# Wireless_Motor_Driver_Shield.net
KiCad netlist of a schematic drawn in EAGLE
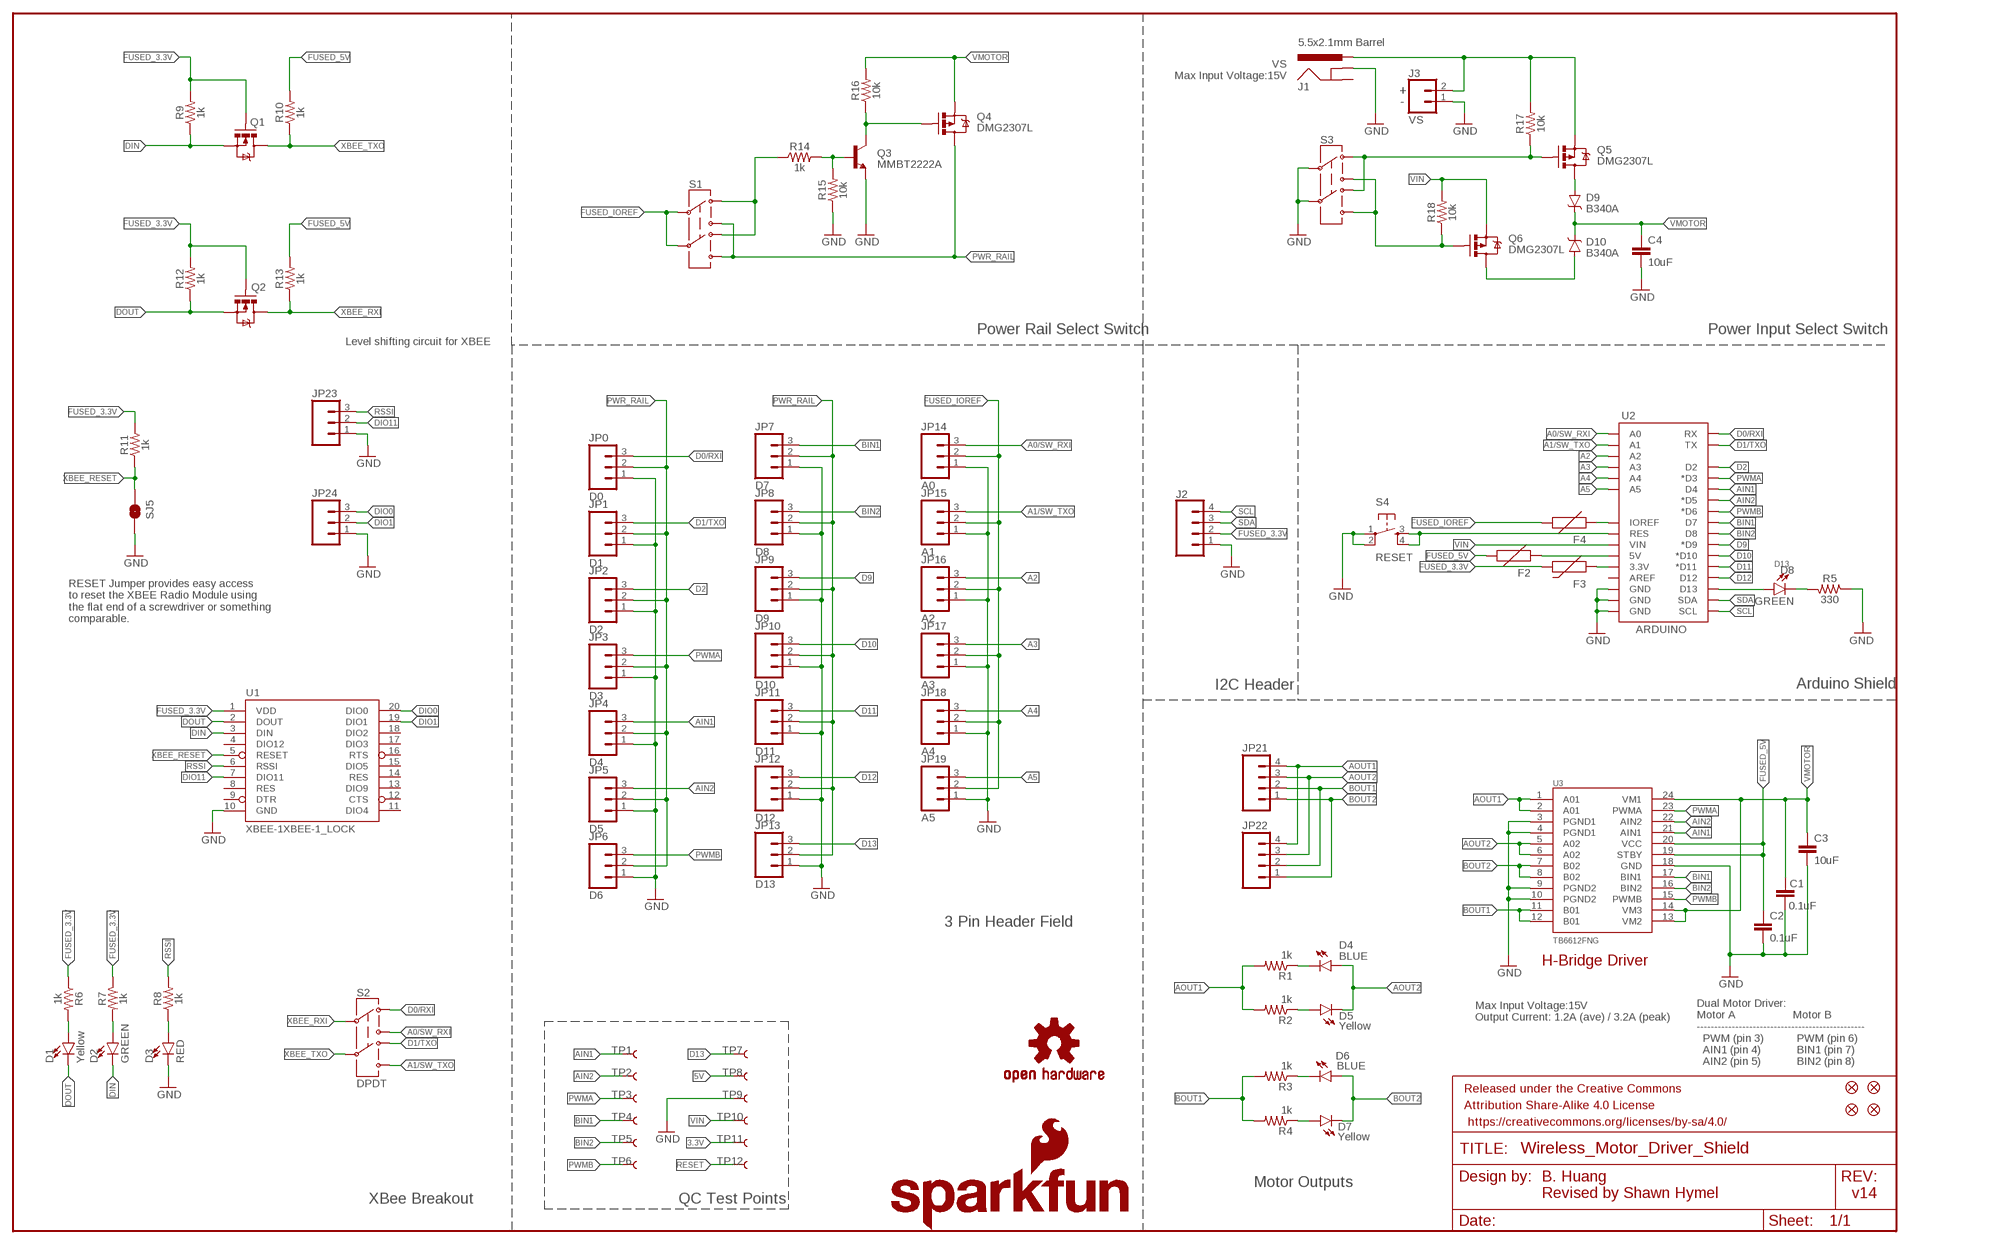
[diagram p0: schematic, sheet 1]

(export (version "E")
  (design (tool "Eeschema 10.0.6"))
  (components
    (comp (ref "C1")
      (value "0.1uF")
      (footprint "eagle-import:0603")
      (libsource (lib "eagle-import") (part "0.1UF-0603-25V-5%"))
    )
    (comp (ref "C2")
      (value "0.1uF")
      (footprint "eagle-import:0603")
      (libsource (lib "eagle-import") (part "0.1UF-0603-25V-5%"))
    )
    (comp (ref "C3")
      (value "10uF")
      (footprint "eagle-import:1210")
      (libsource (lib "eagle-import") (part "10UF-1210-50V-20%"))
    )
    (comp (ref "C4")
      (value "10uF")
      (footprint "eagle-import:1210")
      (libsource (lib "eagle-import") (part "10UF-1210-50V-20%"))
    )
    (comp (ref "D1")
      (value "Yellow")
      (footprint "eagle-import:LED-0603")
      (libsource (lib "eagle-import") (part "LED-YELLOW0603"))
    )
    (comp (ref "D2")
      (value "GREEN")
      (footprint "eagle-import:LED-0603")
      (libsource (lib "eagle-import") (part "LED-GREEN0603"))
    )
    (comp (ref "D3")
      (value "RED")
      (footprint "eagle-import:LED-0603")
      (libsource (lib "eagle-import") (part "LED-RED0603"))
    )
    (comp (ref "D4")
      (value "BLUE")
      (footprint "eagle-import:LED-0603")
      (libsource (lib "eagle-import") (part "LED-BLUE0603"))
    )
    (comp (ref "D5")
      (value "Yellow")
      (footprint "eagle-import:LED-0603")
      (libsource (lib "eagle-import") (part "LED-YELLOW0603"))
    )
    (comp (ref "D6")
      (value "BLUE")
      (footprint "eagle-import:LED-0603")
      (libsource (lib "eagle-import") (part "LED-BLUE0603"))
    )
    (comp (ref "D7")
      (value "Yellow")
      (footprint "eagle-import:LED-0603")
      (libsource (lib "eagle-import") (part "LED-YELLOW0603"))
    )
    (comp (ref "D8")
      (value "GREEN")
      (footprint "eagle-import:LED-0603")
      (libsource (lib "eagle-import") (part "LED-GREEN0603"))
    )
    (comp (ref "D9")
      (value "B340A")
      (footprint "eagle-import:SMA-DIODE")
      (libsource (lib "eagle-import") (part "DIODE-SCHOTTKY-B340A"))
    )
    (comp (ref "D10")
      (value "B340A")
      (footprint "eagle-import:SMA-DIODE")
      (libsource (lib "eagle-import") (part "DIODE-SCHOTTKY-B340A"))
    )
    (comp (ref "F2")
      (value "PTCSMD")
      (footprint "eagle-import:PTC-1206")
      (libsource (lib "eagle-import") (part "PTCSMD"))
    )
    (comp (ref "F3")
      (value "PTCSMD")
      (footprint "eagle-import:PTC-1206")
      (libsource (lib "eagle-import") (part "PTCSMD"))
    )
    (comp (ref "F4")
      (value "PTCSMD")
      (footprint "eagle-import:PTC-1206")
      (libsource (lib "eagle-import") (part "PTCSMD"))
    )
    (comp (ref "FID1")
      (value "FIDUCIAL1X2")
      (footprint "eagle-import:FIDUCIAL-1X2")
      (libsource (lib "eagle-import") (part "FIDUCIAL1X2"))
    )
    (comp (ref "FID2")
      (value "FIDUCIAL1X2")
      (footprint "eagle-import:FIDUCIAL-1X2")
      (libsource (lib "eagle-import") (part "FIDUCIAL1X2"))
    )
    (comp (ref "FID3")
      (value "FIDUCIAL1X2")
      (footprint "eagle-import:FIDUCIAL-1X2")
      (libsource (lib "eagle-import") (part "FIDUCIAL1X2"))
    )
    (comp (ref "FID4")
      (value "FIDUCIAL1X2")
      (footprint "eagle-import:FIDUCIAL-1X2")
      (libsource (lib "eagle-import") (part "FIDUCIAL1X2"))
    )
    (comp (ref "FRAME1")
      (value "FRAME-LEDGER")
      (footprint "eagle-import:CREATIVE_COMMONS")
      (libsource (lib "eagle-import") (part "FRAME-LEDGER"))
    )
    (comp (ref "J1")
      (value "5.5x2.1mm Barrel")
      (footprint "eagle-import:POWER_JACK_SMD")
      (libsource (lib "eagle-import") (part "POWER_JACKSMD"))
    )
    (comp (ref "J2")
      (value "CONN_04SMD_RA_FEMALE")
      (footprint "eagle-import:1X04_SMD_RA_FEMALE")
      (libsource (lib "eagle-import") (part "CONN_04SMD_RA_FEMALE"))
    )
    (comp (ref "J3")
      (value "CONN_021X02_NO_SILK")
      (footprint "eagle-import:1X02_NO_SILK")
      (libsource (lib "eagle-import") (part "CONN_021X02_NO_SILK"))
    )
    (comp (ref "JP0")
      (value "D0")
      (footprint "eagle-import:1X03_LOCK")
      (libsource (lib "eagle-import") (part "M03LOCK"))
    )
    (comp (ref "JP1")
      (value "D1")
      (footprint "eagle-import:1X03_LOCK")
      (libsource (lib "eagle-import") (part "M03LOCK"))
    )
    (comp (ref "JP2")
      (value "D2")
      (footprint "eagle-import:1X03_LOCK")
      (libsource (lib "eagle-import") (part "M03LOCK"))
    )
    (comp (ref "JP3")
      (value "D3")
      (footprint "eagle-import:1X03_LOCK")
      (libsource (lib "eagle-import") (part "M03LOCK"))
    )
    (comp (ref "JP4")
      (value "D4")
      (footprint "eagle-import:1X03_LOCK")
      (libsource (lib "eagle-import") (part "M03LOCK"))
    )
    (comp (ref "JP5")
      (value "D5")
      (footprint "eagle-import:1X03_LOCK")
      (libsource (lib "eagle-import") (part "M03LOCK"))
    )
    (comp (ref "JP6")
      (value "D6")
      (footprint "eagle-import:1X03_LOCK")
      (libsource (lib "eagle-import") (part "M03LOCK"))
    )
    (comp (ref "JP7")
      (value "D7")
      (footprint "eagle-import:1X03_LOCK")
      (libsource (lib "eagle-import") (part "M03LOCK"))
    )
    (comp (ref "JP8")
      (value "D8")
      (footprint "eagle-import:1X03_LOCK")
      (libsource (lib "eagle-import") (part "M03LOCK"))
    )
    (comp (ref "JP9")
      (value "D9")
      (footprint "eagle-import:1X03_LOCK")
      (libsource (lib "eagle-import") (part "M03LOCK"))
    )
    (comp (ref "JP10")
      (value "D10")
      (footprint "eagle-import:1X03_LOCK")
      (libsource (lib "eagle-import") (part "M03LOCK"))
    )
    (comp (ref "JP11")
      (value "D11")
      (footprint "eagle-import:1X03_LOCK")
      (libsource (lib "eagle-import") (part "M03LOCK"))
    )
    (comp (ref "JP12")
      (value "D12")
      (footprint "eagle-import:1X03_LOCK")
      (libsource (lib "eagle-import") (part "M03LOCK"))
    )
    (comp (ref "JP13")
      (value "D13")
      (footprint "eagle-import:1X03_LOCK")
      (libsource (lib "eagle-import") (part "M03LOCK"))
    )
    (comp (ref "JP14")
      (value "A0")
      (footprint "eagle-import:1X03_LOCK")
      (libsource (lib "eagle-import") (part "M03LOCK"))
    )
    (comp (ref "JP15")
      (value "A1")
      (footprint "eagle-import:1X03_LOCK")
      (libsource (lib "eagle-import") (part "M03LOCK"))
    )
    (comp (ref "JP16")
      (value "A2")
      (footprint "eagle-import:1X03_LOCK")
      (libsource (lib "eagle-import") (part "M03LOCK"))
    )
    (comp (ref "JP17")
      (value "A3")
      (footprint "eagle-import:1X03_LOCK")
      (libsource (lib "eagle-import") (part "M03LOCK"))
    )
    (comp (ref "JP18")
      (value "A4")
      (footprint "eagle-import:1X03_LOCK")
      (libsource (lib "eagle-import") (part "M03LOCK"))
    )
    (comp (ref "JP19")
      (value "A5")
      (footprint "eagle-import:1X03_LOCK")
      (libsource (lib "eagle-import") (part "M03LOCK"))
    )
    (comp (ref "JP21")
      (value "M04PTH")
      (footprint "eagle-import:1X04@1")
      (libsource (lib "eagle-import") (part "M04PTH"))
    )
    (comp (ref "JP22")
      (value "M04LOCK")
      (footprint "eagle-import:1X04_LOCK@1")
      (libsource (lib "eagle-import") (part "M04LOCK"))
    )
    (comp (ref "JP23")
      (value "M031X03_NO_SILK")
      (footprint "eagle-import:1X03_NO_SILK")
      (libsource (lib "eagle-import") (part "M031X03_NO_SILK"))
    )
    (comp (ref "JP24")
      (value "M031X03_NO_SILK")
      (footprint "eagle-import:1X03_NO_SILK")
      (libsource (lib "eagle-import") (part "M031X03_NO_SILK"))
    )
    (comp (ref "LOGO1")
      (value "OSHW-LOGOM")
      (footprint "eagle-import:OSHW-LOGO-M")
      (libsource (lib "eagle-import") (part "OSHW-LOGOM"))
    )
    (comp (ref "LOGO2")
      (value "SFE_LOGO_NAME_FLAME.1_INCH")
      (footprint "eagle-import:SFE_LOGO_NAME_FLAME_.1")
      (libsource (lib "eagle-import") (part "SFE_LOGO_NAME_FLAME.1_INCH"))
    )
    (comp (ref "LOGO3")
      (value "SFE_LOGO_FLAME.2_INCH")
      (footprint "eagle-import:SFE_LOGO_FLAME_.2")
      (libsource (lib "eagle-import") (part "SFE_LOGO_FLAME.2_INCH"))
    )
    (comp (ref "LOGO4")
      (value "SFE_LOGO_NAME_FLAME.1_INCH")
      (footprint "eagle-import:SFE_LOGO_NAME_FLAME_.1")
      (libsource (lib "eagle-import") (part "SFE_LOGO_NAME_FLAME.1_INCH"))
    )
    (comp (ref "Q1")
      (value "MOSFET-NCHANNELBSS138")
      (footprint "eagle-import:SOT23-3")
      (libsource (lib "eagle-import") (part "MOSFET-NCHANNELBSS138"))
    )
    (comp (ref "Q2")
      (value "MOSFET-NCHANNELBSS138")
      (footprint "eagle-import:SOT23-3")
      (libsource (lib "eagle-import") (part "MOSFET-NCHANNELBSS138"))
    )
    (comp (ref "Q3")
      (value "MMBT2222A")
      (footprint "eagle-import:SOT23-3")
      (libsource (lib "eagle-import") (part "TRANSISTOR_NPNMMBT2222A"))
    )
    (comp (ref "Q4")
      (value "DMG2307L")
      (footprint "eagle-import:SOT23-3")
      (libsource (lib "eagle-import") (part "MOSFET-PCHANNELDMG2307L"))
    )
    (comp (ref "Q5")
      (value "DMG2307L")
      (footprint "eagle-import:SOT23-3")
      (libsource (lib "eagle-import") (part "MOSFET-PCHANNELDMG2307L"))
    )
    (comp (ref "Q6")
      (value "DMG2307L")
      (footprint "eagle-import:SOT23-3")
      (libsource (lib "eagle-import") (part "MOSFET-PCHANNELDMG2307L"))
    )
    (comp (ref "R1")
      (value "1k")
      (footprint "eagle-import:0603")
      (libsource (lib "eagle-import") (part "1KOHM-0603-1/10W-1%"))
    )
    (comp (ref "R2")
      (value "1k")
      (footprint "eagle-import:0603")
      (libsource (lib "eagle-import") (part "1KOHM-0603-1/10W-1%"))
    )
    (comp (ref "R3")
      (value "1k")
      (footprint "eagle-import:0603")
      (libsource (lib "eagle-import") (part "1KOHM-0603-1/10W-1%"))
    )
    (comp (ref "R4")
      (value "1k")
      (footprint "eagle-import:0603")
      (libsource (lib "eagle-import") (part "1KOHM-0603-1/10W-1%"))
    )
    (comp (ref "R5")
      (value "330")
      (footprint "eagle-import:0603")
      (libsource (lib "eagle-import") (part "330OHM-0603-1/10W-1%"))
    )
    (comp (ref "R6")
      (value "1k")
      (footprint "eagle-import:0603")
      (libsource (lib "eagle-import") (part "1KOHM-0603-1/10W-1%"))
    )
    (comp (ref "R7")
      (value "1k")
      (footprint "eagle-import:0603")
      (libsource (lib "eagle-import") (part "1KOHM-0603-1/10W-1%"))
    )
    (comp (ref "R8")
      (value "1k")
      (footprint "eagle-import:0603")
      (libsource (lib "eagle-import") (part "1KOHM-0603-1/10W-1%"))
    )
    (comp (ref "R9")
      (value "1k")
      (footprint "eagle-import:0603")
      (libsource (lib "eagle-import") (part "1KOHM-0603-1/10W-1%"))
    )
    (comp (ref "R10")
      (value "1k")
      (footprint "eagle-import:0603")
      (libsource (lib "eagle-import") (part "1KOHM-0603-1/10W-1%"))
    )
    (comp (ref "R11")
      (value "1k")
      (footprint "eagle-import:0603")
      (libsource (lib "eagle-import") (part "1KOHM-0603-1/10W-1%"))
    )
    (comp (ref "R12")
      (value "1k")
      (footprint "eagle-import:0603")
      (libsource (lib "eagle-import") (part "1KOHM-0603-1/10W-1%"))
    )
    (comp (ref "R13")
      (value "1k")
      (footprint "eagle-import:0603")
      (libsource (lib "eagle-import") (part "1KOHM-0603-1/10W-1%"))
    )
    (comp (ref "R14")
      (value "1k")
      (footprint "eagle-import:0603")
      (libsource (lib "eagle-import") (part "1KOHM-0603-1/10W-1%"))
    )
    (comp (ref "R15")
      (value "10k")
      (footprint "eagle-import:0603")
      (libsource (lib "eagle-import") (part "10KOHM-0603-1/10W-1%"))
    )
    (comp (ref "R16")
      (value "10k")
      (footprint "eagle-import:0603")
      (libsource (lib "eagle-import") (part "10KOHM-0603-1/10W-1%"))
    )
    (comp (ref "R17")
      (value "10k")
      (footprint "eagle-import:0603")
      (libsource (lib "eagle-import") (part "10KOHM-0603-1/10W-1%"))
    )
    (comp (ref "R18")
      (value "10k")
      (footprint "eagle-import:0603")
      (libsource (lib "eagle-import") (part "10KOHM-0603-1/10W-1%"))
    )
    (comp (ref "S1")
      (value "SWITCH-DPDTAYZ0202")
      (footprint "eagle-import:AYZ0202")
      (libsource (lib "eagle-import") (part "SWITCH-DPDTAYZ0202"))
    )
    (comp (ref "S2")
      (value "DPDT")
      (footprint "eagle-import:AYZ0202")
      (fields (field (name "PROD_ID") "SWCH-08179"))
      (libsource (lib "eagle-import") (part "SWITCH-DPDTAYZ0202"))
    )
    (comp (ref "S3")
      (value "SWITCH-DPDTAYZ0202")
      (footprint "eagle-import:AYZ0202")
      (libsource (lib "eagle-import") (part "SWITCH-DPDTAYZ0202"))
    )
    (comp (ref "S4")
      (value "RESET")
      (footprint "eagle-import:TACTILE-SWITCH-SMD")
      (libsource (lib "eagle-import") (part "TAC_SWITCHSMD"))
    )
    (comp (ref "SJ5")
      (value "SOLDERJUMPERNO")
      (footprint "eagle-import:SJ_2S-NO")
      (libsource (lib "eagle-import") (part "SOLDERJUMPERNO"))
    )
    (comp (ref "TP1")
      (value "TEST-POINT3X5")
      (footprint "eagle-import:PAD.03X.05")
      (libsource (lib "eagle-import") (part "TEST-POINT3X5"))
    )
    (comp (ref "TP2")
      (value "TEST-POINT3X5")
      (footprint "eagle-import:PAD.03X.05")
      (libsource (lib "eagle-import") (part "TEST-POINT3X5"))
    )
    (comp (ref "TP3")
      (value "TEST-POINT3X5")
      (footprint "eagle-import:PAD.03X.05")
      (libsource (lib "eagle-import") (part "TEST-POINT3X5"))
    )
    (comp (ref "TP4")
      (value "TEST-POINT3X5")
      (footprint "eagle-import:PAD.03X.05")
      (libsource (lib "eagle-import") (part "TEST-POINT3X5"))
    )
    (comp (ref "TP5")
      (value "TEST-POINT3X5")
      (footprint "eagle-import:PAD.03X.05")
      (libsource (lib "eagle-import") (part "TEST-POINT3X5"))
    )
    (comp (ref "TP6")
      (value "TEST-POINT3X5")
      (footprint "eagle-import:PAD.03X.05")
      (libsource (lib "eagle-import") (part "TEST-POINT3X5"))
    )
    (comp (ref "TP7")
      (value "TEST-POINT3X5")
      (footprint "eagle-import:PAD.03X.05")
      (libsource (lib "eagle-import") (part "TEST-POINT3X5"))
    )
    (comp (ref "TP8")
      (value "TEST-POINT3X5")
      (footprint "eagle-import:PAD.03X.05")
      (libsource (lib "eagle-import") (part "TEST-POINT3X5"))
    )
    (comp (ref "TP9")
      (value "TEST-POINT3X5")
      (footprint "eagle-import:PAD.03X.05")
      (libsource (lib "eagle-import") (part "TEST-POINT3X5"))
    )
    (comp (ref "TP10")
      (value "TEST-POINT3X5")
      (footprint "eagle-import:PAD.03X.05")
      (libsource (lib "eagle-import") (part "TEST-POINT3X5"))
    )
    (comp (ref "TP11")
      (value "TEST-POINT3X5")
      (footprint "eagle-import:PAD.03X.05")
      (libsource (lib "eagle-import") (part "TEST-POINT3X5"))
    )
    (comp (ref "TP12")
      (value "TEST-POINT3X5")
      (footprint "eagle-import:PAD.03X.05")
      (libsource (lib "eagle-import") (part "TEST-POINT3X5"))
    )
    (comp (ref "U1")
      (value "XBEE-1XBEE-1_LOCK")
      (footprint "eagle-import:XBEE-1_LOCK")
      (libsource (lib "eagle-import") (part "XBEE-1XBEE-1_LOCK"))
    )
    (comp (ref "U2")
      (value "ARDUINO")
      (footprint "eagle-import:UNO_R3_SHIELD_NOLABELS_LOCK")
      (libsource (lib "eagle-import") (part "ARDUINO_R3_SHIELDUNO_R3_SHIELD_NOLABELS_LOCK"))
    )
    (comp (ref "U3")
      (value "TB6612FNG")
      (footprint "eagle-import:SSOP24")
      (libsource (lib "eagle-import") (part "TB6612FNG"))
    )
  )
  (nets
    (net (code "1") (name "3.3V") (class "Default")
      (node (ref "F3") (pin "1") (pinfunction "1_1") (pintype "bidirectional"))
      (node (ref "TP11") (pin "P$1") (pinfunction "1_P$1") (pintype "bidirectional"))
      (node (ref "U2") (pin "3.3V") (pinfunction "3.3V_3.3V") (pintype "bidirectional"))
    )
    (net (code "2") (name "5V") (class "Default")
      (node (ref "F2") (pin "1") (pinfunction "1_1") (pintype "bidirectional"))
      (node (ref "TP8") (pin "P$1") (pinfunction "1_P$1") (pintype "bidirectional"))
      (node (ref "U2") (pin "5V") (pinfunction "5V_5V") (pintype "bidirectional"))
    )
    (net (code "3") (name "A0{slash}SW_RXI") (class "Default")
      (node (ref "JP14") (pin "3") (pinfunction "3_3") (pintype "passive"))
      (node (ref "S2") (pin "3") (pinfunction "3_3") (pintype "bidirectional"))
      (node (ref "U2") (pin "A0") (pinfunction "A0_A0") (pintype "bidirectional"))
    )
    (net (code "4") (name "A1{slash}SW_TXO") (class "Default")
      (node (ref "JP15") (pin "3") (pinfunction "3_3") (pintype "passive"))
      (node (ref "S2") (pin "6") (pinfunction "6_6") (pintype "bidirectional"))
      (node (ref "U2") (pin "A1") (pinfunction "A1_A1") (pintype "bidirectional"))
    )
    (net (code "5") (name "A2") (class "Default")
      (node (ref "JP16") (pin "3") (pinfunction "3_3") (pintype "passive"))
      (node (ref "U2") (pin "A2") (pinfunction "A2_A2") (pintype "bidirectional"))
    )
    (net (code "6") (name "A3") (class "Default")
      (node (ref "JP17") (pin "3") (pinfunction "3_3") (pintype "passive"))
      (node (ref "U2") (pin "A3") (pinfunction "A3_A3") (pintype "bidirectional"))
    )
    (net (code "7") (name "A4") (class "Default")
      (node (ref "JP18") (pin "3") (pinfunction "3_3") (pintype "passive"))
      (node (ref "U2") (pin "A4") (pinfunction "A4_A4") (pintype "bidirectional"))
    )
    (net (code "8") (name "A5") (class "Default")
      (node (ref "JP19") (pin "3") (pinfunction "3_3") (pintype "passive"))
      (node (ref "U2") (pin "A5") (pinfunction "A5_A5") (pintype "bidirectional"))
    )
    (net (code "9") (name "AIN1") (class "Default")
      (node (ref "JP4") (pin "3") (pinfunction "3_3") (pintype "passive"))
      (node (ref "TP1") (pin "P$1") (pinfunction "1_P$1") (pintype "bidirectional"))
      (node (ref "U2") (pin "D4") (pinfunction "D4_D4") (pintype "bidirectional"))
      (node (ref "U3") (pin "21") (pinfunction "AIN1_21") (pintype "bidirectional"))
    )
    (net (code "10") (name "AIN2") (class "Default")
      (node (ref "JP5") (pin "3") (pinfunction "3_3") (pintype "passive"))
      (node (ref "TP2") (pin "P$1") (pinfunction "1_P$1") (pintype "bidirectional"))
      (node (ref "U2") (pin "D5") (pinfunction "*D5_D5") (pintype "bidirectional"))
      (node (ref "U3") (pin "22") (pinfunction "AIN2_22") (pintype "bidirectional"))
    )
    (net (code "11") (name "AOUT1") (class "Default")
      (node (ref "JP21") (pin "4") (pinfunction "4_4") (pintype "passive"))
      (node (ref "JP22") (pin "4") (pinfunction "4_4") (pintype "passive"))
      (node (ref "R1") (pin "2") (pinfunction "2_2") (pintype "passive"))
      (node (ref "R2") (pin "2") (pinfunction "2_2") (pintype "passive"))
      (node (ref "U3") (pin "1") (pinfunction "A01_1") (pintype "bidirectional"))
      (node (ref "U3") (pin "2") (pinfunction "A01_2") (pintype "bidirectional"))
    )
    (net (code "12") (name "AOUT2") (class "Default")
      (node (ref "D4") (pin "A") (pinfunction "A_A") (pintype "passive"))
      (node (ref "D5") (pin "C") (pinfunction "C_C") (pintype "passive"))
      (node (ref "JP21") (pin "3") (pinfunction "3_3") (pintype "passive"))
      (node (ref "JP22") (pin "3") (pinfunction "3_3") (pintype "passive"))
      (node (ref "U3") (pin "5") (pinfunction "A02_5") (pintype "bidirectional"))
      (node (ref "U3") (pin "6") (pinfunction "A02_6") (pintype "bidirectional"))
    )
    (net (code "13") (name "BIN1") (class "Default")
      (node (ref "JP7") (pin "3") (pinfunction "3_3") (pintype "passive"))
      (node (ref "TP4") (pin "P$1") (pinfunction "1_P$1") (pintype "bidirectional"))
      (node (ref "U2") (pin "D7") (pinfunction "D7_D7") (pintype "bidirectional"))
      (node (ref "U3") (pin "17") (pinfunction "BIN1_17") (pintype "bidirectional"))
    )
    (net (code "14") (name "BIN2") (class "Default")
      (node (ref "JP8") (pin "3") (pinfunction "3_3") (pintype "passive"))
      (node (ref "TP5") (pin "P$1") (pinfunction "1_P$1") (pintype "bidirectional"))
      (node (ref "U2") (pin "D8") (pinfunction "D8_D8") (pintype "bidirectional"))
      (node (ref "U3") (pin "16") (pinfunction "BIN2_16") (pintype "bidirectional"))
    )
    (net (code "15") (name "BOUT1") (class "Default")
      (node (ref "JP21") (pin "2") (pinfunction "2_2") (pintype "passive"))
      (node (ref "JP22") (pin "2") (pinfunction "2_2") (pintype "passive"))
      (node (ref "R3") (pin "2") (pinfunction "2_2") (pintype "passive"))
      (node (ref "R4") (pin "2") (pinfunction "2_2") (pintype "passive"))
      (node (ref "U3") (pin "11") (pinfunction "B01_11") (pintype "bidirectional"))
      (node (ref "U3") (pin "12") (pinfunction "B01_12") (pintype "bidirectional"))
    )
    (net (code "16") (name "BOUT2") (class "Default")
      (node (ref "D6") (pin "A") (pinfunction "A_A") (pintype "passive"))
      (node (ref "D7") (pin "C") (pinfunction "C_C") (pintype "passive"))
      (node (ref "JP21") (pin "1") (pinfunction "1_1") (pintype "passive"))
      (node (ref "JP22") (pin "1") (pinfunction "1_1") (pintype "passive"))
      (node (ref "U3") (pin "7") (pinfunction "B02_7") (pintype "bidirectional"))
      (node (ref "U3") (pin "8") (pinfunction "B02_8") (pintype "bidirectional"))
    )
    (net (code "17") (name "D0{slash}RXI") (class "Default")
      (node (ref "JP0") (pin "3") (pinfunction "3_3") (pintype "passive"))
      (node (ref "S2") (pin "1") (pinfunction "1_1") (pintype "bidirectional"))
      (node (ref "U2") (pin "RX") (pinfunction "RX_RX") (pintype "bidirectional"))
    )
    (net (code "18") (name "D1{slash}TXO") (class "Default")
      (node (ref "JP1") (pin "3") (pinfunction "3_3") (pintype "passive"))
      (node (ref "S2") (pin "4") (pinfunction "4_4") (pintype "bidirectional"))
      (node (ref "U2") (pin "TX") (pinfunction "TX_TX") (pintype "bidirectional"))
    )
    (net (code "19") (name "D2") (class "Default")
      (node (ref "JP2") (pin "3") (pinfunction "3_3") (pintype "passive"))
      (node (ref "U2") (pin "D2") (pinfunction "D2_D2") (pintype "bidirectional"))
    )
    (net (code "20") (name "D9") (class "Default")
      (node (ref "JP9") (pin "3") (pinfunction "3_3") (pintype "passive"))
      (node (ref "U2") (pin "D9") (pinfunction "*D9_D9") (pintype "bidirectional"))
    )
    (net (code "21") (name "D10") (class "Default")
      (node (ref "JP10") (pin "3") (pinfunction "3_3") (pintype "passive"))
      (node (ref "U2") (pin "D10") (pinfunction "*D10_D10") (pintype "bidirectional"))
    )
    (net (code "22") (name "D11") (class "Default")
      (node (ref "JP11") (pin "3") (pinfunction "3_3") (pintype "passive"))
      (node (ref "U2") (pin "D11") (pinfunction "*D11_D11") (pintype "bidirectional"))
    )
    (net (code "23") (name "D12") (class "Default")
      (node (ref "JP12") (pin "3") (pinfunction "3_3") (pintype "passive"))
      (node (ref "U2") (pin "D12") (pinfunction "D12_D12") (pintype "bidirectional"))
    )
    (net (code "24") (name "D13") (class "Default")
      (node (ref "D8") (pin "A") (pinfunction "A_A") (pintype "passive"))
      (node (ref "JP13") (pin "3") (pinfunction "3_3") (pintype "passive"))
      (node (ref "TP7") (pin "P$1") (pinfunction "1_P$1") (pintype "bidirectional"))
      (node (ref "U2") (pin "D13") (pinfunction "D13_D13") (pintype "bidirectional"))
    )
    (net (code "25") (name "DIN") (class "Default")
      (node (ref "D2") (pin "C") (pinfunction "C_C") (pintype "passive"))
      (node (ref "Q1") (pin "2") (pinfunction "S_2") (pintype "passive"))
      (node (ref "R9") (pin "1") (pinfunction "1_1") (pintype "passive"))
      (node (ref "U1") (pin "3") (pinfunction "DIN_3") (pintype "input"))
    )
    (net (code "26") (name "DIO0") (class "Default")
      (node (ref "JP24") (pin "3") (pinfunction "3_3") (pintype "passive"))
      (node (ref "U1") (pin "20") (pinfunction "DIO0_20") (pintype "bidirectional"))
    )
    (net (code "27") (name "DIO1") (class "Default")
      (node (ref "JP24") (pin "2") (pinfunction "2_2") (pintype "passive"))
      (node (ref "U1") (pin "19") (pinfunction "DIO1_19") (pintype "bidirectional"))
    )
    (net (code "28") (name "DIO11") (class "Default")
      (node (ref "JP23") (pin "2") (pinfunction "2_2") (pintype "passive"))
      (node (ref "U1") (pin "7") (pinfunction "DIO11_7") (pintype "bidirectional"))
    )
    (net (code "29") (name "DOUT") (class "Default")
      (node (ref "D1") (pin "C") (pinfunction "C_C") (pintype "passive"))
      (node (ref "Q2") (pin "2") (pinfunction "S_2") (pintype "passive"))
      (node (ref "R12") (pin "1") (pinfunction "1_1") (pintype "passive"))
      (node (ref "U1") (pin "2") (pinfunction "DOUT_2") (pintype "output"))
    )
    (net (code "30") (name "FUSED_3.3V") (class "Default")
      (node (ref "F3") (pin "2") (pinfunction "2_2") (pintype "bidirectional"))
      (node (ref "J2") (pin "2") (pinfunction "2_2") (pintype "passive"))
      (node (ref "Q1") (pin "1") (pinfunction "G_1") (pintype "passive"))
      (node (ref "Q2") (pin "1") (pinfunction "G_1") (pintype "passive"))
      (node (ref "R11") (pin "2") (pinfunction "2_2") (pintype "passive"))
      (node (ref "R12") (pin "2") (pinfunction "2_2") (pintype "passive"))
      (node (ref "R6") (pin "1") (pinfunction "1_1") (pintype "passive"))
      (node (ref "R7") (pin "1") (pinfunction "1_1") (pintype "passive"))
      (node (ref "R9") (pin "2") (pinfunction "2_2") (pintype "passive"))
      (node (ref "U1") (pin "1") (pinfunction "VDD_1") (pintype "power_in"))
    )
    (net (code "31") (name "FUSED_5V") (class "Default")
      (node (ref "C2") (pin "1") (pinfunction "1_1") (pintype "passive"))
      (node (ref "F2") (pin "2") (pinfunction "2_2") (pintype "bidirectional"))
      (node (ref "R10") (pin "2") (pinfunction "2_2") (pintype "passive"))
      (node (ref "R13") (pin "2") (pinfunction "2_2") (pintype "passive"))
      (node (ref "U3") (pin "19") (pinfunction "STBY_19") (pintype "bidirectional"))
      (node (ref "U3") (pin "20") (pinfunction "VCC_20") (pintype "bidirectional"))
    )
    (net (code "32") (name "FUSED_IOREF") (class "Default")
      (node (ref "F4") (pin "2") (pinfunction "2_2") (pintype "bidirectional"))
      (node (ref "JP14") (pin "2") (pinfunction "2_2") (pintype "passive"))
      (node (ref "JP15") (pin "2") (pinfunction "2_2") (pintype "passive"))
      (node (ref "JP16") (pin "2") (pinfunction "2_2") (pintype "passive"))
      (node (ref "JP17") (pin "2") (pinfunction "2_2") (pintype "passive"))
      (node (ref "JP18") (pin "2") (pinfunction "2_2") (pintype "passive"))
      (node (ref "JP19") (pin "2") (pinfunction "2_2") (pintype "passive"))
      (node (ref "S1") (pin "2") (pinfunction "2_2") (pintype "bidirectional"))
      (node (ref "S1") (pin "5") (pinfunction "5_5") (pintype "bidirectional"))
    )
    (net (code "33") (name "GND") (class "Default")
      (node (ref "C1") (pin "2") (pinfunction "2_2") (pintype "passive"))
      (node (ref "C2") (pin "2") (pinfunction "2_2") (pintype "passive"))
      (node (ref "C3") (pin "2") (pinfunction "2_2") (pintype "passive"))
      (node (ref "C4") (pin "2") (pinfunction "2_2") (pintype "passive"))
      (node (ref "D3") (pin "C") (pinfunction "C_C") (pintype "passive"))
      (node (ref "J1") (pin "GND") (pinfunction "GNDBREAK_GND") (pintype "bidirectional"))
      (node (ref "J2") (pin "1") (pinfunction "1_1") (pintype "passive"))
      (node (ref "J3") (pin "1") (pinfunction "1_1") (pintype "passive"))
      (node (ref "JP0") (pin "1") (pinfunction "1_1") (pintype "passive"))
      (node (ref "JP1") (pin "1") (pinfunction "1_1") (pintype "passive"))
      (node (ref "JP10") (pin "1") (pinfunction "1_1") (pintype "passive"))
      (node (ref "JP11") (pin "1") (pinfunction "1_1") (pintype "passive"))
      (node (ref "JP12") (pin "1") (pinfunction "1_1") (pintype "passive"))
      (node (ref "JP13") (pin "1") (pinfunction "1_1") (pintype "passive"))
      (node (ref "JP14") (pin "1") (pinfunction "1_1") (pintype "passive"))
      (node (ref "JP15") (pin "1") (pinfunction "1_1") (pintype "passive"))
      (node (ref "JP16") (pin "1") (pinfunction "1_1") (pintype "passive"))
      (node (ref "JP17") (pin "1") (pinfunction "1_1") (pintype "passive"))
      (node (ref "JP18") (pin "1") (pinfunction "1_1") (pintype "passive"))
      (node (ref "JP19") (pin "1") (pinfunction "1_1") (pintype "passive"))
      (node (ref "JP2") (pin "1") (pinfunction "1_1") (pintype "passive"))
      (node (ref "JP23") (pin "1") (pinfunction "1_1") (pintype "passive"))
      (node (ref "JP24") (pin "1") (pinfunction "1_1") (pintype "passive"))
      (node (ref "JP3") (pin "1") (pinfunction "1_1") (pintype "passive"))
      (node (ref "JP4") (pin "1") (pinfunction "1_1") (pintype "passive"))
      (node (ref "JP5") (pin "1") (pinfunction "1_1") (pintype "passive"))
      (node (ref "JP6") (pin "1") (pinfunction "1_1") (pintype "passive"))
      (node (ref "JP7") (pin "1") (pinfunction "1_1") (pintype "passive"))
      (node (ref "JP8") (pin "1") (pinfunction "1_1") (pintype "passive"))
      (node (ref "JP9") (pin "1") (pinfunction "1_1") (pintype "passive"))
      (node (ref "Q3") (pin "2") (pinfunction "E_2") (pintype "passive"))
      (node (ref "R15") (pin "1") (pinfunction "1_1") (pintype "passive"))
      (node (ref "R5") (pin "1") (pinfunction "1_1") (pintype "passive"))
      (node (ref "S3") (pin "2") (pinfunction "2_2") (pintype "bidirectional"))
      (node (ref "S3") (pin "5") (pinfunction "5_5") (pintype "bidirectional"))
      (node (ref "S4") (pin "1") (pinfunction "1_1") (pintype "passive"))
      (node (ref "S4") (pin "2") (pinfunction "2_2") (pintype "passive"))
      (node (ref "SJ5") (pin "2") (pinfunction "2_2") (pintype "passive"))
      (node (ref "TP9") (pin "P$1") (pinfunction "1_P$1") (pintype "bidirectional"))
      (node (ref "U1") (pin "10") (pinfunction "GND_10") (pintype "power_in"))
      (node (ref "U2") (pin "GND@0") (pinfunction "GND_GND@0") (pintype "bidirectional"))
      (node (ref "U2") (pin "GND@1") (pinfunction "GND_GND@1") (pintype "bidirectional"))
      (node (ref "U2") (pin "GND@2") (pinfunction "GND_GND@2") (pintype "bidirectional"))
      (node (ref "U3") (pin "10") (pinfunction "PGND2_10") (pintype "bidirectional"))
      (node (ref "U3") (pin "18") (pinfunction "GND_18") (pintype "bidirectional"))
      (node (ref "U3") (pin "3") (pinfunction "PGND1_3") (pintype "bidirectional"))
      (node (ref "U3") (pin "4") (pinfunction "PGND1_4") (pintype "bidirectional"))
      (node (ref "U3") (pin "9") (pinfunction "PGND2_9") (pintype "bidirectional"))
    )
    (net (code "34") (name "Net-(D1-PadA)") (class "Default")
      (node (ref "D1") (pin "A") (pinfunction "A_A") (pintype "passive"))
      (node (ref "R6") (pin "2") (pinfunction "2_2") (pintype "passive"))
    )
    (net (code "35") (name "Net-(D2-PadA)") (class "Default")
      (node (ref "D2") (pin "A") (pinfunction "A_A") (pintype "passive"))
      (node (ref "R7") (pin "2") (pinfunction "2_2") (pintype "passive"))
    )
    (net (code "36") (name "Net-(D3-PadA)") (class "Default")
      (node (ref "D3") (pin "A") (pinfunction "A_A") (pintype "passive"))
      (node (ref "R8") (pin "1") (pinfunction "1_1") (pintype "passive"))
    )
    (net (code "37") (name "Net-(D4-PadC)") (class "Default")
      (node (ref "D4") (pin "C") (pinfunction "C_C") (pintype "passive"))
      (node (ref "R1") (pin "1") (pinfunction "1_1") (pintype "passive"))
    )
    (net (code "38") (name "Net-(D5-PadA)") (class "Default")
      (node (ref "D5") (pin "A") (pinfunction "A_A") (pintype "passive"))
      (node (ref "R2") (pin "1") (pinfunction "1_1") (pintype "passive"))
    )
    (net (code "39") (name "Net-(D6-PadC)") (class "Default")
      (node (ref "D6") (pin "C") (pinfunction "C_C") (pintype "passive"))
      (node (ref "R3") (pin "1") (pinfunction "1_1") (pintype "passive"))
    )
    (net (code "40") (name "Net-(D7-PadA)") (class "Default")
      (node (ref "D7") (pin "A") (pinfunction "A_A") (pintype "passive"))
      (node (ref "R4") (pin "1") (pinfunction "1_1") (pintype "passive"))
    )
    (net (code "41") (name "Net-(D8-PadC)") (class "Default")
      (node (ref "D8") (pin "C") (pinfunction "C_C") (pintype "passive"))
      (node (ref "R5") (pin "2") (pinfunction "2_2") (pintype "passive"))
    )
    (net (code "42") (name "Net-(F4-Pad1)") (class "Default")
      (node (ref "F4") (pin "1") (pinfunction "1_1") (pintype "bidirectional"))
      (node (ref "U2") (pin "IOREF") (pinfunction "IOREF_IOREF") (pintype "bidirectional"))
    )
    (net (code "43") (name "Net-(J1-PWR)") (class "Default")
      (node (ref "J1") (pin "VIN0") (pinfunction "PWR_VIN0") (pintype "bidirectional"))
      (node (ref "J3") (pin "2") (pinfunction "2_2") (pintype "passive"))
      (node (ref "Q5") (pin "2") (pinfunction "S_2") (pintype "passive"))
      (node (ref "R17") (pin "2") (pinfunction "2_2") (pintype "passive"))
    )
    (net (code "44") (name "Net-(Q3-B)") (class "Default")
      (node (ref "Q3") (pin "1") (pinfunction "B_1") (pintype "passive"))
      (node (ref "R14") (pin "2") (pinfunction "2_2") (pintype "passive"))
      (node (ref "R15") (pin "2") (pinfunction "2_2") (pintype "passive"))
    )
    (net (code "45") (name "Net-(Q3-C)") (class "Default")
      (node (ref "Q3") (pin "3") (pinfunction "C_3") (pintype "passive"))
      (node (ref "Q4") (pin "1") (pinfunction "G_1") (pintype "passive"))
      (node (ref "R16") (pin "1") (pinfunction "1_1") (pintype "passive"))
    )
    (net (code "46") (name "Net-(Q5-D)") (class "Default")
      (node (ref "D9") (pin "A") (pinfunction "A_A") (pintype "passive"))
      (node (ref "Q5") (pin "3") (pinfunction "D_3") (pintype "passive"))
    )
    (net (code "47") (name "Net-(Q5-G)") (class "Default")
      (node (ref "Q5") (pin "1") (pinfunction "G_1") (pintype "passive"))
      (node (ref "R17") (pin "1") (pinfunction "1_1") (pintype "passive"))
      (node (ref "S3") (pin "1") (pinfunction "1_1") (pintype "bidirectional"))
      (node (ref "S3") (pin "4") (pinfunction "4_4") (pintype "bidirectional"))
    )
    (net (code "48") (name "Net-(Q6-D)") (class "Default")
      (node (ref "D10") (pin "A") (pinfunction "A_A") (pintype "passive"))
      (node (ref "Q6") (pin "3") (pinfunction "D_3") (pintype "passive"))
    )
    (net (code "49") (name "Net-(Q6-G)") (class "Default")
      (node (ref "Q6") (pin "1") (pinfunction "G_1") (pintype "passive"))
      (node (ref "R18") (pin "1") (pinfunction "1_1") (pintype "passive"))
      (node (ref "S3") (pin "3") (pinfunction "3_3") (pintype "bidirectional"))
      (node (ref "S3") (pin "6") (pinfunction "6_6") (pintype "bidirectional"))
    )
    (net (code "50") (name "Net-(R14-Pad1)") (class "Default")
      (node (ref "R14") (pin "1") (pinfunction "1_1") (pintype "passive"))
      (node (ref "S1") (pin "1") (pinfunction "1_1") (pintype "bidirectional"))
      (node (ref "S1") (pin "4") (pinfunction "4_4") (pintype "bidirectional"))
    )
    (net (code "51") (name "PWMA") (class "Default")
      (node (ref "JP3") (pin "3") (pinfunction "3_3") (pintype "passive"))
      (node (ref "TP3") (pin "P$1") (pinfunction "1_P$1") (pintype "bidirectional"))
      (node (ref "U2") (pin "D3") (pinfunction "*D3_D3") (pintype "bidirectional"))
      (node (ref "U3") (pin "23") (pinfunction "PWMA_23") (pintype "bidirectional"))
    )
    (net (code "52") (name "PWMB") (class "Default")
      (node (ref "JP6") (pin "3") (pinfunction "3_3") (pintype "passive"))
      (node (ref "TP6") (pin "P$1") (pinfunction "1_P$1") (pintype "bidirectional"))
      (node (ref "U2") (pin "D6") (pinfunction "*D6_D6") (pintype "bidirectional"))
      (node (ref "U3") (pin "15") (pinfunction "PWMB_15") (pintype "bidirectional"))
    )
    (net (code "53") (name "PWR_RAIL") (class "Default")
      (node (ref "JP0") (pin "2") (pinfunction "2_2") (pintype "passive"))
      (node (ref "JP1") (pin "2") (pinfunction "2_2") (pintype "passive"))
      (node (ref "JP10") (pin "2") (pinfunction "2_2") (pintype "passive"))
      (node (ref "JP11") (pin "2") (pinfunction "2_2") (pintype "passive"))
      (node (ref "JP12") (pin "2") (pinfunction "2_2") (pintype "passive"))
      (node (ref "JP13") (pin "2") (pinfunction "2_2") (pintype "passive"))
      (node (ref "JP2") (pin "2") (pinfunction "2_2") (pintype "passive"))
      (node (ref "JP3") (pin "2") (pinfunction "2_2") (pintype "passive"))
      (node (ref "JP4") (pin "2") (pinfunction "2_2") (pintype "passive"))
      (node (ref "JP5") (pin "2") (pinfunction "2_2") (pintype "passive"))
      (node (ref "JP6") (pin "2") (pinfunction "2_2") (pintype "passive"))
      (node (ref "JP7") (pin "2") (pinfunction "2_2") (pintype "passive"))
      (node (ref "JP8") (pin "2") (pinfunction "2_2") (pintype "passive"))
      (node (ref "JP9") (pin "2") (pinfunction "2_2") (pintype "passive"))
      (node (ref "Q4") (pin "3") (pinfunction "D_3") (pintype "passive"))
      (node (ref "S1") (pin "3") (pinfunction "3_3") (pintype "bidirectional"))
      (node (ref "S1") (pin "6") (pinfunction "6_6") (pintype "bidirectional"))
    )
    (net (code "54") (name "RESET") (class "Default")
      (node (ref "S4") (pin "3") (pinfunction "3_3") (pintype "passive"))
      (node (ref "S4") (pin "4") (pinfunction "4_4") (pintype "passive"))
      (node (ref "TP12") (pin "P$1") (pinfunction "1_P$1") (pintype "bidirectional"))
      (node (ref "U2") (pin "RES") (pinfunction "RES_RES") (pintype "bidirectional"))
    )
    (net (code "55") (name "RSSI") (class "Default")
      (node (ref "JP23") (pin "3") (pinfunction "3_3") (pintype "passive"))
      (node (ref "R8") (pin "2") (pinfunction "2_2") (pintype "passive"))
      (node (ref "U1") (pin "6") (pinfunction "RSSI_6") (pintype "bidirectional"))
    )
    (net (code "56") (name "SCL") (class "Default")
      (node (ref "J2") (pin "4") (pinfunction "4_4") (pintype "passive"))
      (node (ref "U2") (pin "SCL") (pinfunction "SCL_SCL") (pintype "bidirectional"))
    )
    (net (code "57") (name "SDA") (class "Default")
      (node (ref "J2") (pin "3") (pinfunction "3_3") (pintype "passive"))
      (node (ref "U2") (pin "SDA") (pinfunction "SDA_SDA") (pintype "bidirectional"))
    )
    (net (code "58") (name "VIN") (class "Default")
      (node (ref "Q6") (pin "2") (pinfunction "S_2") (pintype "passive"))
      (node (ref "R18") (pin "2") (pinfunction "2_2") (pintype "passive"))
      (node (ref "TP10") (pin "P$1") (pinfunction "1_P$1") (pintype "bidirectional"))
      (node (ref "U2") (pin "VIN") (pinfunction "VIN_VIN") (pintype "bidirectional"))
    )
    (net (code "59") (name "VMOTOR") (class "Default")
      (node (ref "C1") (pin "1") (pinfunction "1_1") (pintype "passive"))
      (node (ref "C3") (pin "1") (pinfunction "1_1") (pintype "passive"))
      (node (ref "C4") (pin "1") (pinfunction "1_1") (pintype "passive"))
      (node (ref "D10") (pin "C") (pinfunction "C_C") (pintype "passive"))
      (node (ref "D9") (pin "C") (pinfunction "C_C") (pintype "passive"))
      (node (ref "Q4") (pin "2") (pinfunction "S_2") (pintype "passive"))
      (node (ref "R16") (pin "2") (pinfunction "2_2") (pintype "passive"))
      (node (ref "U3") (pin "13") (pinfunction "VM2_13") (pintype "bidirectional"))
      (node (ref "U3") (pin "14") (pinfunction "VM3_14") (pintype "bidirectional"))
      (node (ref "U3") (pin "24") (pinfunction "VM1_24") (pintype "bidirectional"))
    )
    (net (code "60") (name "XBEE_RESET") (class "Default")
      (node (ref "R11") (pin "1") (pinfunction "1_1") (pintype "passive"))
      (node (ref "SJ5") (pin "1") (pinfunction "1_1") (pintype "passive"))
      (node (ref "U1") (pin "5") (pinfunction "RESET_5") (pintype "input"))
    )
    (net (code "61") (name "XBEE_RXI") (class "Default")
      (node (ref "Q2") (pin "3") (pinfunction "D_3") (pintype "passive"))
      (node (ref "R13") (pin "1") (pinfunction "1_1") (pintype "passive"))
      (node (ref "S2") (pin "2") (pinfunction "2_2") (pintype "bidirectional"))
    )
    (net (code "62") (name "XBEE_TXO") (class "Default")
      (node (ref "Q1") (pin "3") (pinfunction "D_3") (pintype "passive"))
      (node (ref "R10") (pin "1") (pinfunction "1_1") (pintype "passive"))
      (node (ref "S2") (pin "5") (pinfunction "5_5") (pintype "bidirectional"))
    )
    (net (code "63") (name "unconnected-(J1-GND-PadP$4)") (class "Default")
      (node (ref "J1") (pin "P$4") (pinfunction "GND_P$4") (pintype "bidirectional"))
    )
    (net (code "64") (name "unconnected-(U1-CTS-Pad12)") (class "Default")
      (node (ref "U1") (pin "12") (pinfunction "CTS_12") (pintype "output"))
    )
    (net (code "65") (name "unconnected-(U1-DIO2-Pad18)") (class "Default")
      (node (ref "U1") (pin "18") (pinfunction "DIO2_18") (pintype "bidirectional"))
    )
    (net (code "66") (name "unconnected-(U1-DIO3-Pad17)") (class "Default")
      (node (ref "U1") (pin "17") (pinfunction "DIO3_17") (pintype "bidirectional"))
    )
    (net (code "67") (name "unconnected-(U1-DIO4-Pad11)") (class "Default")
      (node (ref "U1") (pin "11") (pinfunction "DIO4_11") (pintype "bidirectional"))
    )
    (net (code "68") (name "unconnected-(U1-DIO5-Pad15)") (class "Default")
      (node (ref "U1") (pin "15") (pinfunction "DIO5_15") (pintype "bidirectional"))
    )
    (net (code "69") (name "unconnected-(U1-DIO9-Pad13)") (class "Default")
      (node (ref "U1") (pin "13") (pinfunction "DIO9_13") (pintype "bidirectional"))
    )
    (net (code "70") (name "unconnected-(U1-DIO12-Pad4)") (class "Default")
      (node (ref "U1") (pin "4") (pinfunction "DIO12_4") (pintype "bidirectional"))
    )
    (net (code "71") (name "unconnected-(U1-DTR-Pad9)") (class "Default")
      (node (ref "U1") (pin "9") (pinfunction "DTR_9") (pintype "bidirectional"))
    )
    (net (code "72") (name "unconnected-(U1-RES-Pad8)") (class "Default")
      (node (ref "U1") (pin "8") (pinfunction "RES_8") (pintype "bidirectional"))
    )
    (net (code "73") (name "unconnected-(U1-RES-Pad14)") (class "Default")
      (node (ref "U1") (pin "14") (pinfunction "RES_14") (pintype "bidirectional"))
    )
    (net (code "74") (name "unconnected-(U1-RTS-Pad16)") (class "Default")
      (node (ref "U1") (pin "16") (pinfunction "RTS_16") (pintype "input"))
    )
    (net (code "75") (name "unconnected-(U2-PadAREF)") (class "Default")
      (node (ref "U2") (pin "AREF") (pinfunction "AREF_AREF") (pintype "bidirectional"))
    )
  )
)
